# Sheet2.net
KiCad netlist of a schematic drawn in Altium Designer
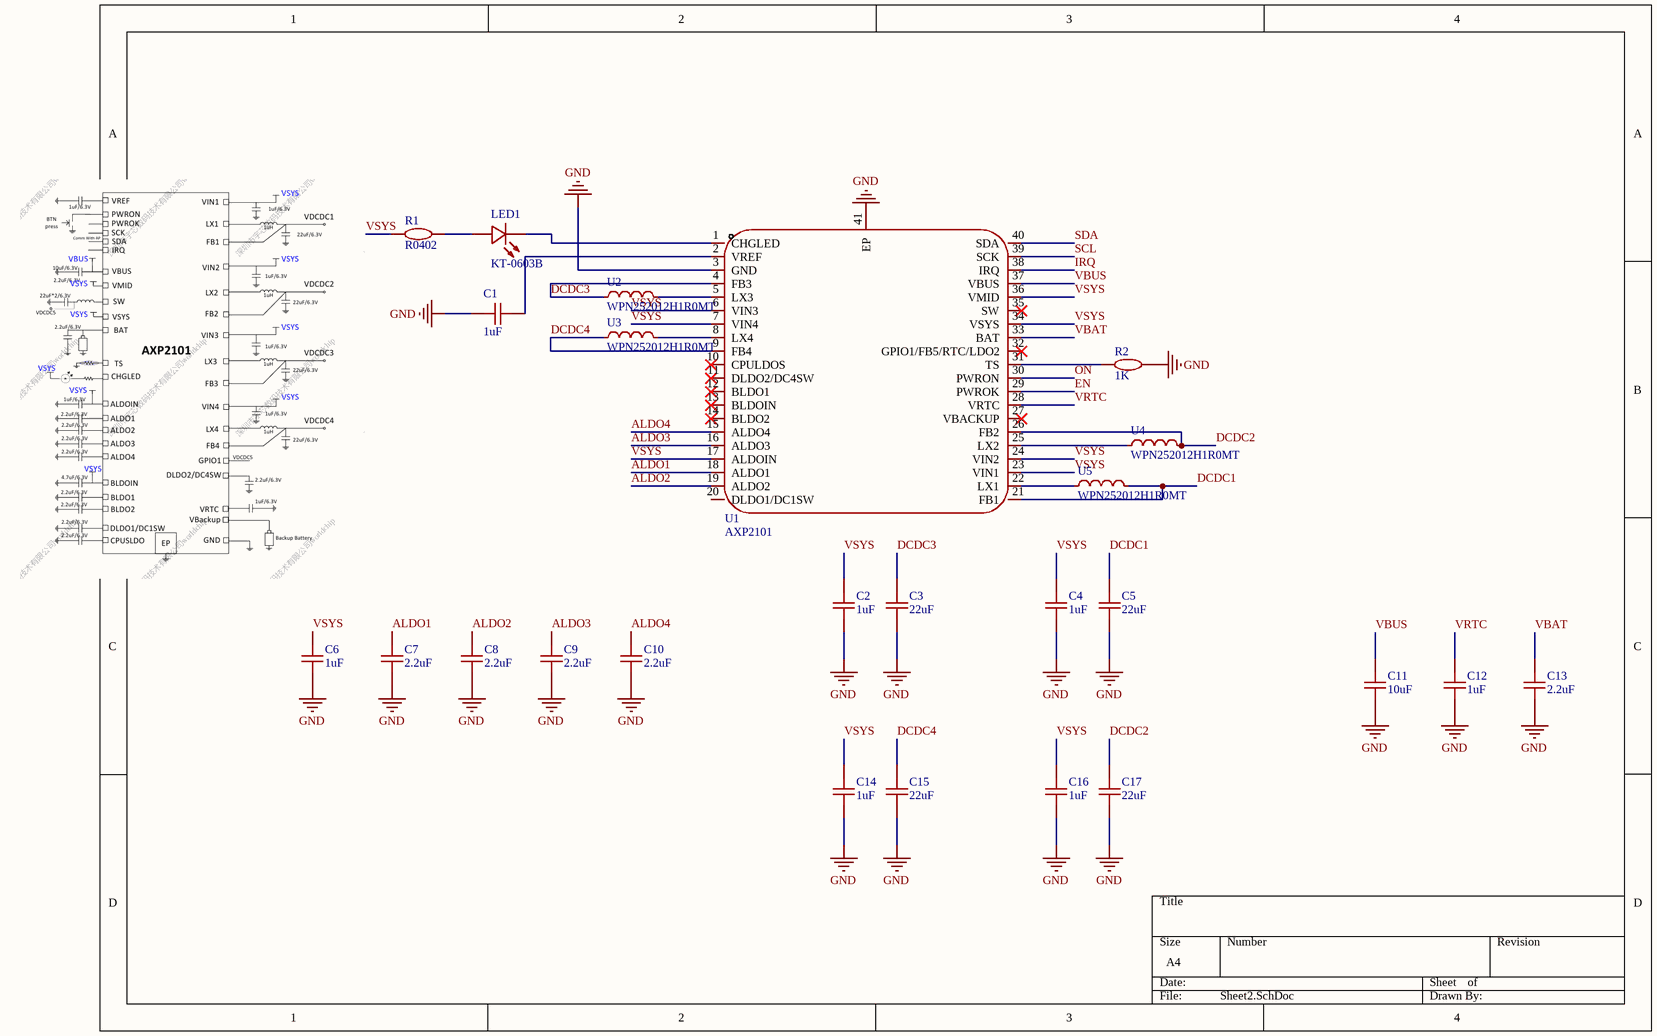
[diagram p0: Sheet2.SchDoc]

(export (version "E")
  (design (tool "Eeschema 10.0.6"))
  (components
    (comp (ref "C1") (value "1uF") (footprint "C0402") (libsource (lib "RLC") (part "C0402")))
    (comp (ref "C2") (value "1uF") (footprint "C0402") (libsource (lib "RLC") (part "C0402")))
    (comp (ref "C3") (value "22uF") (footprint "C0603") (libsource (lib "RLC") (part "C0603")))
    (comp (ref "C4") (value "1uF") (footprint "C0402") (libsource (lib "RLC") (part "C0402")))
    (comp (ref "C5") (value "22uF") (footprint "C0603") (libsource (lib "RLC") (part "C0603")))
    (comp (ref "C6") (value "1uF") (footprint "C0402") (libsource (lib "RLC") (part "C0402")))
    (comp (ref "C7") (value "2.2uF") (footprint "C0402") (libsource (lib "RLC") (part "C0402")))
    (comp (ref "C8") (value "2.2uF") (footprint "C0402") (libsource (lib "RLC") (part "C0402")))
    (comp (ref "C9") (value "2.2uF") (footprint "C0402") (libsource (lib "RLC") (part "C0402")))
    (comp (ref "C10") (value "2.2uF") (footprint "C0402") (libsource (lib "RLC") (part "C0402")))
    (comp (ref "C11") (value "10uF") (footprint "C0603") (libsource (lib "RLC") (part "C0603")))
    (comp (ref "C12") (value "1uF") (footprint "C0402") (libsource (lib "RLC") (part "C0402")))
    (comp (ref "C13") (value "2.2uF") (footprint "C0402") (libsource (lib "RLC") (part "C0402")))
    (comp (ref "C14") (value "1uF") (footprint "C0402") (libsource (lib "RLC") (part "C0402")))
    (comp (ref "C15") (value "22uF") (footprint "C0603") (libsource (lib "RLC") (part "C0603")))
    (comp (ref "C16") (value "1uF") (footprint "C0402") (libsource (lib "RLC") (part "C0402")))
    (comp (ref "C17") (value "22uF") (footprint "C0603") (libsource (lib "RLC") (part "C0603")))
    (comp (ref "LED1") (value "KT-0603B") (footprint "LED0603-BL") (libsource (lib "LED") (part "KT-0603B")))
    (comp (ref "R1") (value "R0402") (footprint "R0402") (libsource (lib "RLC") (part "R0402")))
    (comp (ref "R2") (value "1K") (footprint "R0402") (libsource (lib "RLC") (part "R0402")))
    (comp (ref "U1")
      (value "AXP2101")
      (footprint "QFN-40_L5.0-W5.0-P0.40-TL-EP3.4")
      (libsource (lib "IC") (part "AXP2101"))
    )
    (comp (ref "U2")
      (value "WPN252012H1R0MT")
      (footprint "IND-SMD_L2.5-W2.0_WPN252012H")
      (description "1uH")
      (libsource (lib "RLC") (part "WPN252012H1R0MT"))
    )
    (comp (ref "U3")
      (value "WPN252012H1R0MT")
      (footprint "IND-SMD_L2.5-W2.0_WPN252012H")
      (description "1uH")
      (libsource (lib "RLC") (part "WPN252012H1R0MT"))
    )
    (comp (ref "U4")
      (value "WPN252012H1R0MT")
      (footprint "IND-SMD_L2.5-W2.0_WPN252012H")
      (description "1uH")
      (libsource (lib "RLC") (part "WPN252012H1R0MT"))
    )
    (comp (ref "U5")
      (value "WPN252012H1R0MT")
      (footprint "IND-SMD_L2.5-W2.0_WPN252012H")
      (description "1uH")
      (libsource (lib "RLC") (part "WPN252012H1R0MT"))
    )
  )
  (nets
    (net (code "1") (name "/ALDO1") (class "Default")
      (node (ref "C7") (pin "2") (pinfunction "2_2") (pintype "passive"))
      (node (ref "U1") (pin "18") (pinfunction "ALDO1_18") (pintype "passive"))
    )
    (net (code "2") (name "/ALDO2") (class "Default")
      (node (ref "C8") (pin "2") (pinfunction "2_2") (pintype "passive"))
      (node (ref "U1") (pin "19") (pinfunction "ALDO2_19") (pintype "passive"))
    )
    (net (code "3") (name "/ALDO3") (class "Default")
      (node (ref "C9") (pin "2") (pinfunction "2_2") (pintype "passive"))
      (node (ref "U1") (pin "16") (pinfunction "ALDO3_16") (pintype "passive"))
    )
    (net (code "4") (name "/ALDO4") (class "Default")
      (node (ref "C10") (pin "2") (pinfunction "2_2") (pintype "passive"))
      (node (ref "U1") (pin "15") (pinfunction "ALDO4_15") (pintype "passive"))
    )
    (net (code "5") (name "/DCDC1") (class "Default")
      (node (ref "C5") (pin "2") (pinfunction "2_2") (pintype "passive"))
      (node (ref "U1") (pin "21") (pinfunction "FB1_21") (pintype "passive"))
      (node (ref "U5") (pin "2") (pinfunction "2_2") (pintype "passive"))
    )
    (net (code "6") (name "/DCDC2") (class "Default")
      (node (ref "C17") (pin "2") (pinfunction "2_2") (pintype "passive"))
      (node (ref "U1") (pin "26") (pinfunction "FB2_26") (pintype "passive"))
      (node (ref "U4") (pin "2") (pinfunction "2_2") (pintype "passive"))
    )
    (net (code "7") (name "/DCDC3") (class "Default")
      (node (ref "C3") (pin "2") (pinfunction "2_2") (pintype "passive"))
      (node (ref "U1") (pin "4") (pinfunction "FB3_4") (pintype "passive"))
      (node (ref "U2") (pin "1") (pinfunction "1_1") (pintype "passive"))
    )
    (net (code "8") (name "/DCDC4") (class "Default")
      (node (ref "C15") (pin "2") (pinfunction "2_2") (pintype "passive"))
      (node (ref "U1") (pin "9") (pinfunction "FB4_9") (pintype "passive"))
      (node (ref "U3") (pin "1") (pinfunction "1_1") (pintype "passive"))
    )
    (net (code "9") (name "/EN") (class "Default")
      (node (ref "U1") (pin "29") (pinfunction "PWROK_29") (pintype "passive"))
    )
    (net (code "10") (name "/IRQ") (class "Default")
      (node (ref "U1") (pin "38") (pinfunction "IRQ_38") (pintype "passive"))
    )
    (net (code "11") (name "/ON") (class "Default")
      (node (ref "U1") (pin "30") (pinfunction "PWRON_30") (pintype "passive"))
    )
    (net (code "12") (name "/SCL") (class "Default")
      (node (ref "U1") (pin "39") (pinfunction "SCK_39") (pintype "passive"))
    )
    (net (code "13") (name "/SDA") (class "Default")
      (node (ref "U1") (pin "40") (pinfunction "SDA_40") (pintype "passive"))
    )
    (net (code "14") (name "/VBAT") (class "Default")
      (node (ref "C13") (pin "2") (pinfunction "2_2") (pintype "passive"))
      (node (ref "U1") (pin "33") (pinfunction "BAT_33") (pintype "passive"))
    )
    (net (code "15") (name "/VBUS") (class "Default")
      (node (ref "C11") (pin "2") (pinfunction "2_2") (pintype "passive"))
      (node (ref "U1") (pin "37") (pinfunction "VBUS_37") (pintype "passive"))
    )
    (net (code "16") (name "/VRTC") (class "Default")
      (node (ref "C12") (pin "2") (pinfunction "2_2") (pintype "passive"))
      (node (ref "U1") (pin "28") (pinfunction "VRTC_28") (pintype "passive"))
    )
    (net (code "17") (name "/VSYS") (class "Default")
      (node (ref "C14") (pin "2") (pinfunction "2_2") (pintype "passive"))
      (node (ref "C16") (pin "2") (pinfunction "2_2") (pintype "passive"))
      (node (ref "C2") (pin "2") (pinfunction "2_2") (pintype "passive"))
      (node (ref "C4") (pin "2") (pinfunction "2_2") (pintype "passive"))
      (node (ref "C6") (pin "2") (pinfunction "2_2") (pintype "passive"))
      (node (ref "R1") (pin "1") (pinfunction "1_1") (pintype "passive"))
      (node (ref "U1") (pin "17") (pinfunction "ALDOIN_17") (pintype "passive"))
      (node (ref "U1") (pin "23") (pinfunction "VIN1_23") (pintype "passive"))
      (node (ref "U1") (pin "24") (pinfunction "VIN2_24") (pintype "passive"))
      (node (ref "U1") (pin "34") (pinfunction "VSYS_34") (pintype "passive"))
      (node (ref "U1") (pin "36") (pinfunction "VMID_36") (pintype "passive"))
      (node (ref "U1") (pin "6") (pinfunction "VIN3_6") (pintype "passive"))
      (node (ref "U1") (pin "7") (pinfunction "VIN4_7") (pintype "passive"))
    )
    (net (code "18") (name "GND") (class "Default")
      (node (ref "C1") (pin "1") (pinfunction "1_1") (pintype "passive"))
      (node (ref "C10") (pin "1") (pinfunction "1_1") (pintype "passive"))
      (node (ref "C11") (pin "1") (pinfunction "1_1") (pintype "passive"))
      (node (ref "C12") (pin "1") (pinfunction "1_1") (pintype "passive"))
      (node (ref "C13") (pin "1") (pinfunction "1_1") (pintype "passive"))
      (node (ref "C14") (pin "1") (pinfunction "1_1") (pintype "passive"))
      (node (ref "C15") (pin "1") (pinfunction "1_1") (pintype "passive"))
      (node (ref "C16") (pin "1") (pinfunction "1_1") (pintype "passive"))
      (node (ref "C17") (pin "1") (pinfunction "1_1") (pintype "passive"))
      (node (ref "C2") (pin "1") (pinfunction "1_1") (pintype "passive"))
      (node (ref "C3") (pin "1") (pinfunction "1_1") (pintype "passive"))
      (node (ref "C4") (pin "1") (pinfunction "1_1") (pintype "passive"))
      (node (ref "C5") (pin "1") (pinfunction "1_1") (pintype "passive"))
      (node (ref "C6") (pin "1") (pinfunction "1_1") (pintype "passive"))
      (node (ref "C7") (pin "1") (pinfunction "1_1") (pintype "passive"))
      (node (ref "C8") (pin "1") (pinfunction "1_1") (pintype "passive"))
      (node (ref "C9") (pin "1") (pinfunction "1_1") (pintype "passive"))
      (node (ref "R2") (pin "2") (pinfunction "2_2") (pintype "passive"))
      (node (ref "U1") (pin "3") (pinfunction "GND_3") (pintype "passive"))
      (node (ref "U1") (pin "41") (pinfunction "EP_41") (pintype "passive"))
    )
    (net (code "19") (name "Net-(LED1-A)") (class "Default")
      (node (ref "LED1") (pin "2") (pinfunction "A_2") (pintype "passive"))
      (node (ref "R1") (pin "2") (pinfunction "2_2") (pintype "passive"))
    )
    (net (code "20") (name "Net-(LED1-K)") (class "Default")
      (node (ref "LED1") (pin "1") (pinfunction "K_1") (pintype "passive"))
      (node (ref "U1") (pin "1") (pinfunction "CHGLED_1") (pintype "passive"))
    )
    (net (code "21") (name "Net-(U1-LX1)") (class "Default")
      (node (ref "U1") (pin "22") (pinfunction "LX1_22") (pintype "passive"))
      (node (ref "U5") (pin "1") (pinfunction "1_1") (pintype "passive"))
    )
    (net (code "22") (name "Net-(U1-LX2)") (class "Default")
      (node (ref "U1") (pin "25") (pinfunction "LX2_25") (pintype "passive"))
      (node (ref "U4") (pin "1") (pinfunction "1_1") (pintype "passive"))
    )
    (net (code "23") (name "Net-(U1-LX3)") (class "Default")
      (node (ref "U1") (pin "5") (pinfunction "LX3_5") (pintype "passive"))
      (node (ref "U2") (pin "2") (pinfunction "2_2") (pintype "passive"))
    )
    (net (code "24") (name "Net-(U1-LX4)") (class "Default")
      (node (ref "U1") (pin "8") (pinfunction "LX4_8") (pintype "passive"))
      (node (ref "U3") (pin "2") (pinfunction "2_2") (pintype "passive"))
    )
    (net (code "25") (name "Net-(U1-TS)") (class "Default")
      (node (ref "R2") (pin "1") (pinfunction "1_1") (pintype "passive"))
      (node (ref "U1") (pin "31") (pinfunction "TS_31") (pintype "passive"))
    )
    (net (code "26") (name "Net-(U1-VREF)") (class "Default")
      (node (ref "C1") (pin "2") (pinfunction "2_2") (pintype "passive"))
      (node (ref "U1") (pin "2") (pinfunction "VREF_2") (pintype "passive"))
    )
    (net (code "27") (name "unconnected-(U1-BLDO1-Pad12)") (class "Default")
      (node (ref "U1") (pin "12") (pinfunction "BLDO1_12") (pintype "passive+no_connect"))
    )
    (net (code "28") (name "unconnected-(U1-BLDO2-Pad14)") (class "Default")
      (node (ref "U1") (pin "14") (pinfunction "BLDO2_14") (pintype "passive+no_connect"))
    )
    (net (code "29") (name "unconnected-(U1-BLDOIN-Pad13)") (class "Default")
      (node (ref "U1") (pin "13") (pinfunction "BLDOIN_13") (pintype "passive+no_connect"))
    )
    (net (code "30") (name "unconnected-(U1-CPULDOS-Pad10)") (class "Default")
      (node (ref "U1") (pin "10") (pinfunction "CPULDOS_10") (pintype "passive+no_connect"))
    )
    (net (code "31") (name "unconnected-(U1-DLDO1{slash}DC1SW-Pad20)") (class "Default")
      (node (ref "U1") (pin "20") (pinfunction "DLDO1/DC1SW_20") (pintype "passive"))
    )
    (net (code "32") (name "unconnected-(U1-DLDO2{slash}DC4SW-Pad11)") (class "Default")
      (node (ref "U1") (pin "11") (pinfunction "DLDO2/DC4SW_11") (pintype "passive+no_connect"))
    )
    (net (code "33") (name "unconnected-(U1-GPIO1{slash}FB5{slash}RTC{slash}LDO2-Pad32)") (class "Default")
      (node (ref "U1") (pin "32") (pinfunction "GPIO1/FB5/RTC/LDO2_32") (pintype "passive+no_connect"))
    )
    (net (code "34") (name "unconnected-(U1-SW-Pad35)") (class "Default")
      (node (ref "U1") (pin "35") (pinfunction "SW_35") (pintype "passive+no_connect"))
    )
    (net (code "35") (name "unconnected-(U1-VBACKUP-Pad27)") (class "Default")
      (node (ref "U1") (pin "27") (pinfunction "VBACKUP_27") (pintype "passive+no_connect"))
    )
  )
)
